# PWR.net
KiCad netlist of a schematic drawn in Altium Designer
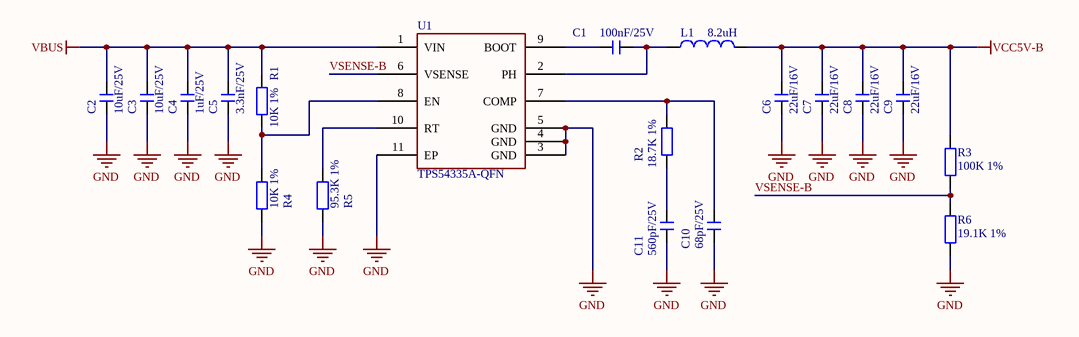
[diagram p0: PWR.SchDoc]

(export (version "E")
  (design (tool "Eeschema 10.0.6"))
  (components
    (comp (ref "C1")
      (value "100nF/25V")
      (footprint "C0402_L")
      (description "无极性贴片电容")
      (fields (field (name "版权归属") "源创客"))
      (libsource (lib "Capacitor") (part "C"))
    )
    (comp (ref "C2")
      (value "10uF/25V")
      (footprint "C0603_L")
      (description "无极性贴片电容")
      (fields (field (name "版权归属") "源创客"))
      (libsource (lib "Capacitor") (part "C"))
    )
    (comp (ref "C3")
      (value "10uF/25V")
      (footprint "C0603_L")
      (description "无极性贴片电容")
      (fields (field (name "版权归属") "源创客"))
      (libsource (lib "Capacitor") (part "C"))
    )
    (comp (ref "C4")
      (value "1uF/25V")
      (footprint "C0603_L")
      (description "无极性贴片电容")
      (fields (field (name "版权归属") "源创客"))
      (libsource (lib "Capacitor") (part "C"))
    )
    (comp (ref "C5")
      (value "3.3nF/25V")
      (footprint "C0603_L")
      (description "无极性贴片电容")
      (fields (field (name "版权归属") "源创客"))
      (libsource (lib "Capacitor") (part "C"))
    )
    (comp (ref "C6")
      (value "22uF/16V")
      (footprint "C0603_L")
      (description "无极性贴片电容")
      (fields (field (name "版权归属") "源创客"))
      (libsource (lib "Capacitor") (part "C"))
    )
    (comp (ref "C7")
      (value "22uF/16V")
      (footprint "C0603_L")
      (description "无极性贴片电容")
      (fields (field (name "版权归属") "源创客"))
      (libsource (lib "Capacitor") (part "C"))
    )
    (comp (ref "C8")
      (value "22uF/16V")
      (footprint "C0603_L")
      (description "无极性贴片电容")
      (fields (field (name "版权归属") "源创客"))
      (libsource (lib "Capacitor") (part "C"))
    )
    (comp (ref "C9")
      (value "22uF/16V")
      (footprint "C0603_L")
      (description "无极性贴片电容")
      (fields (field (name "版权归属") "源创客"))
      (libsource (lib "Capacitor") (part "C"))
    )
    (comp (ref "C10")
      (value "68pF/25V")
      (footprint "C0402_L")
      (description "无极性贴片电容")
      (fields (field (name "版权归属") "源创客"))
      (libsource (lib "Capacitor") (part "C"))
    )
    (comp (ref "C11")
      (value "560pF/25V")
      (footprint "C0402_L")
      (description "无极性贴片电容")
      (fields (field (name "版权归属") "源创客"))
      (libsource (lib "Capacitor") (part "C"))
    )
    (comp (ref "L1")
      (value "8.2uH")
      (footprint "NR4020")
      (description "小功率贴片电感")
      (fields (field (name "版权归属") "源创客"))
      (libsource (lib "Inductor") (part "L"))
    )
    (comp (ref "R1")
      (value "10K 1%")
      (footprint "R0402_L")
      (description "贴片电阻")
      (fields (field (name "版权归属") "源创客"))
      (libsource (lib "Resistor") (part "R"))
    )
    (comp (ref "R2")
      (value "18.7K 1%")
      (footprint "R0402_L")
      (description "贴片电阻")
      (fields (field (name "版权归属") "源创客"))
      (libsource (lib "Resistor") (part "R"))
    )
    (comp (ref "R3")
      (value "100K 1%")
      (footprint "R0402_L")
      (description "贴片电阻")
      (fields (field (name "版权归属") "源创客"))
      (libsource (lib "Resistor") (part "R"))
    )
    (comp (ref "R4")
      (value "10K 1%")
      (footprint "R0402_L")
      (description "贴片电阻")
      (fields (field (name "版权归属") "源创客"))
      (libsource (lib "Resistor") (part "R"))
    )
    (comp (ref "R5")
      (value "95.3K 1%")
      (footprint "R0402_L")
      (description "贴片电阻")
      (fields (field (name "版权归属") "源创客"))
      (libsource (lib "Resistor") (part "R"))
    )
    (comp (ref "R6")
      (value "19.1K 1%")
      (footprint "R0402_L")
      (description "贴片电阻")
      (fields (field (name "版权归属") "源创客"))
      (libsource (lib "Resistor") (part "R"))
    )
    (comp (ref "U1")
      (value "TPS54335A-QFN")
      (footprint "VSON-10_L3.0-W3.0-P0.50-TL-EP")
      (description "BUCK")
      (libsource (lib "DCDC Convert") (part "TPS54335A-QFN"))
    )
  )
  (nets
    (net (code "1") (name "/VSENSE-B") (class "Default")
      (node (ref "R3") (pin "2") (pinfunction "2_2") (pintype "passive"))
      (node (ref "R6") (pin "1") (pinfunction "1_1") (pintype "passive"))
      (node (ref "U1") (pin "6") (pinfunction "VSENSE_6") (pintype "passive"))
    )
    (net (code "2") (name "GND") (class "Default")
      (node (ref "C10") (pin "1") (pinfunction "1_1") (pintype "passive"))
      (node (ref "C11") (pin "1") (pinfunction "1_1") (pintype "passive"))
      (node (ref "C2") (pin "1") (pinfunction "1_1") (pintype "passive"))
      (node (ref "C3") (pin "1") (pinfunction "1_1") (pintype "passive"))
      (node (ref "C4") (pin "1") (pinfunction "1_1") (pintype "passive"))
      (node (ref "C5") (pin "1") (pinfunction "1_1") (pintype "passive"))
      (node (ref "C6") (pin "1") (pinfunction "1_1") (pintype "passive"))
      (node (ref "C7") (pin "1") (pinfunction "1_1") (pintype "passive"))
      (node (ref "C8") (pin "1") (pinfunction "1_1") (pintype "passive"))
      (node (ref "C9") (pin "1") (pinfunction "1_1") (pintype "passive"))
      (node (ref "R4") (pin "2") (pinfunction "2_2") (pintype "passive"))
      (node (ref "R5") (pin "2") (pinfunction "2_2") (pintype "passive"))
      (node (ref "R6") (pin "2") (pinfunction "2_2") (pintype "passive"))
      (node (ref "U1") (pin "11") (pinfunction "EP_11") (pintype "passive"))
      (node (ref "U1") (pin "3") (pinfunction "GND_3") (pintype "passive"))
      (node (ref "U1") (pin "4") (pinfunction "GND_4") (pintype "passive"))
      (node (ref "U1") (pin "5") (pinfunction "GND_5") (pintype "passive"))
    )
    (net (code "3") (name "Net-(C11-Pad2)") (class "Default")
      (node (ref "C11") (pin "2") (pinfunction "2_2") (pintype "passive"))
      (node (ref "R2") (pin "2") (pinfunction "2_2") (pintype "passive"))
    )
    (net (code "4") (name "Net-(U1-BOOT)") (class "Default")
      (node (ref "C1") (pin "2") (pinfunction "2_2") (pintype "passive"))
      (node (ref "U1") (pin "9") (pinfunction "BOOT_9") (pintype "passive"))
    )
    (net (code "5") (name "Net-(U1-COMP)") (class "Default")
      (node (ref "C10") (pin "2") (pinfunction "2_2") (pintype "passive"))
      (node (ref "R2") (pin "1") (pinfunction "1_1") (pintype "passive"))
      (node (ref "U1") (pin "7") (pinfunction "COMP_7") (pintype "passive"))
    )
    (net (code "6") (name "Net-(U1-EN)") (class "Default")
      (node (ref "R1") (pin "2") (pinfunction "2_2") (pintype "passive"))
      (node (ref "R4") (pin "1") (pinfunction "1_1") (pintype "passive"))
      (node (ref "U1") (pin "8") (pinfunction "EN_8") (pintype "passive"))
    )
    (net (code "7") (name "Net-(U1-PH)") (class "Default")
      (node (ref "C1") (pin "1") (pinfunction "1_1") (pintype "passive"))
      (node (ref "L1") (pin "1") (pinfunction "1_1") (pintype "passive"))
      (node (ref "U1") (pin "2") (pinfunction "PH_2") (pintype "passive"))
    )
    (net (code "8") (name "Net-(U1-RT)") (class "Default")
      (node (ref "R5") (pin "1") (pinfunction "1_1") (pintype "passive"))
      (node (ref "U1") (pin "10") (pinfunction "RT_10") (pintype "passive"))
    )
    (net (code "9") (name "VBUS") (class "Default")
      (node (ref "C2") (pin "2") (pinfunction "2_2") (pintype "passive"))
      (node (ref "C3") (pin "2") (pinfunction "2_2") (pintype "passive"))
      (node (ref "C4") (pin "2") (pinfunction "2_2") (pintype "passive"))
      (node (ref "C5") (pin "2") (pinfunction "2_2") (pintype "passive"))
      (node (ref "R1") (pin "1") (pinfunction "1_1") (pintype "passive"))
      (node (ref "U1") (pin "1") (pinfunction "VIN_1") (pintype "passive"))
    )
    (net (code "10") (name "VCC5V-B") (class "Default")
      (node (ref "C6") (pin "2") (pinfunction "2_2") (pintype "passive"))
      (node (ref "C7") (pin "2") (pinfunction "2_2") (pintype "passive"))
      (node (ref "C8") (pin "2") (pinfunction "2_2") (pintype "passive"))
      (node (ref "C9") (pin "2") (pinfunction "2_2") (pintype "passive"))
      (node (ref "L1") (pin "2") (pinfunction "2_2") (pintype "passive"))
      (node (ref "R3") (pin "1") (pinfunction "1_1") (pintype "passive"))
    )
  )
)
